# relay_ladder.net
KiCad netlist of a schematic drawn in Altium Designer
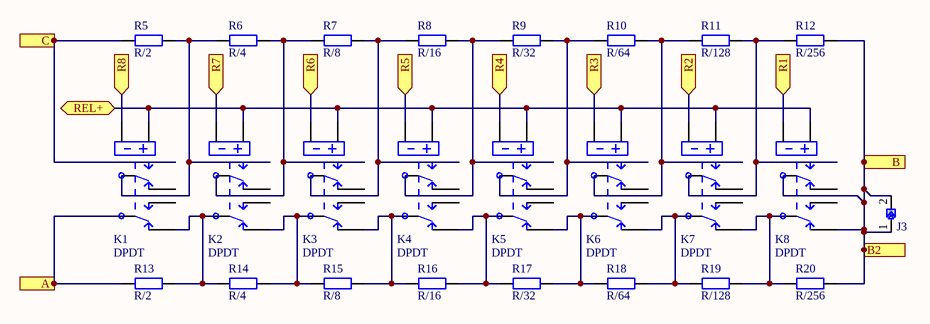
[diagram p0: relay_ladder.SchDoc]

(export (version "E")
  (design (tool "Eeschema 10.0.6"))
  (components
    (comp (ref "J3")
      (value "solder_jumper")
      (footprint "SOLDER_JUMPER_SQUARE")
      (libsource (lib "components_library") (part "solder_jumper"))
    )
    (comp (ref "K1")
      (value "DPDT")
      (footprint "AXICOM IM-G Relay")
      (description "TE CONNECTIVITY  IM-GR  RELAY, DPDT, NO")
      (libsource (lib "components_library") (part "IM-GR Relay DPDT"))
    )
    (comp (ref "K2")
      (value "DPDT")
      (footprint "AXICOM IM-G Relay")
      (description "TE CONNECTIVITY  IM-GR  RELAY, DPDT, NO")
      (libsource (lib "components_library") (part "IM-GR Relay DPDT"))
    )
    (comp (ref "K3")
      (value "DPDT")
      (footprint "AXICOM IM-G Relay")
      (description "TE CONNECTIVITY  IM-GR  RELAY, DPDT, NO")
      (libsource (lib "components_library") (part "IM-GR Relay DPDT"))
    )
    (comp (ref "K4")
      (value "DPDT")
      (footprint "AXICOM IM-G Relay")
      (description "TE CONNECTIVITY  IM-GR  RELAY, DPDT, NO")
      (libsource (lib "components_library") (part "IM-GR Relay DPDT"))
    )
    (comp (ref "K5")
      (value "DPDT")
      (footprint "AXICOM IM-G Relay")
      (description "TE CONNECTIVITY  IM-GR  RELAY, DPDT, NO")
      (libsource (lib "components_library") (part "IM-GR Relay DPDT"))
    )
    (comp (ref "K6")
      (value "DPDT")
      (footprint "AXICOM IM-G Relay")
      (description "TE CONNECTIVITY  IM-GR  RELAY, DPDT, NO")
      (libsource (lib "components_library") (part "IM-GR Relay DPDT"))
    )
    (comp (ref "K7")
      (value "DPDT")
      (footprint "AXICOM IM-G Relay")
      (description "TE CONNECTIVITY  IM-GR  RELAY, DPDT, NO")
      (libsource (lib "components_library") (part "IM-GR Relay DPDT"))
    )
    (comp (ref "K8")
      (value "DPDT")
      (footprint "AXICOM IM-G Relay")
      (description "TE CONNECTIVITY  IM-GR  RELAY, DPDT, NO")
      (libsource (lib "components_library") (part "IM-GR Relay DPDT"))
    )
    (comp (ref "R5")
      (value "R/2")
      (footprint "R2012_0805I_L")
      (description "R")
      (libsource (lib "General") (part "R"))
    )
    (comp (ref "R6")
      (value "R/4")
      (footprint "R2012_0805I_L")
      (description "R")
      (libsource (lib "General") (part "R"))
    )
    (comp (ref "R7")
      (value "R/8")
      (footprint "R2012_0805I_L")
      (description "R")
      (libsource (lib "General") (part "R"))
    )
    (comp (ref "R8")
      (value "R/16")
      (footprint "R2012_0805I_L")
      (description "R")
      (libsource (lib "General") (part "R"))
    )
    (comp (ref "R9")
      (value "R/32")
      (footprint "R2012_0805I_L")
      (description "R")
      (libsource (lib "General") (part "R"))
    )
    (comp (ref "R10")
      (value "R/64")
      (footprint "R2012_0805I_L")
      (description "R")
      (libsource (lib "General") (part "R"))
    )
    (comp (ref "R11")
      (value "R/128")
      (footprint "R2012_0805I_L")
      (description "R")
      (libsource (lib "General") (part "R"))
    )
    (comp (ref "R12")
      (value "R/256")
      (footprint "R2012_0805I_L")
      (description "R")
      (libsource (lib "General") (part "R"))
    )
    (comp (ref "R13")
      (value "R/2")
      (footprint "R2012_0805I_L")
      (description "R")
      (libsource (lib "General") (part "R"))
    )
    (comp (ref "R14")
      (value "R/4")
      (footprint "R2012_0805I_L")
      (description "R")
      (libsource (lib "General") (part "R"))
    )
    (comp (ref "R15")
      (value "R/8")
      (footprint "R2012_0805I_L")
      (description "R")
      (libsource (lib "General") (part "R"))
    )
    (comp (ref "R16")
      (value "R/16")
      (footprint "R2012_0805I_L")
      (description "R")
      (libsource (lib "General") (part "R"))
    )
    (comp (ref "R17")
      (value "R/32")
      (footprint "R2012_0805I_L")
      (description "R")
      (libsource (lib "General") (part "R"))
    )
    (comp (ref "R18")
      (value "R/64")
      (footprint "R2012_0805I_L")
      (description "R")
      (libsource (lib "General") (part "R"))
    )
    (comp (ref "R19")
      (value "R/128")
      (footprint "R2012_0805I_L")
      (description "R")
      (libsource (lib "General") (part "R"))
    )
    (comp (ref "R20")
      (value "R/256")
      (footprint "R2012_0805I_L")
      (description "R")
      (libsource (lib "General") (part "R"))
    )
  )
  (nets
    (net (code "1") (name "/A") (class "Default")
      (node (ref "K1") (pin "6") (pinfunction "6_6") (pintype "passive"))
      (node (ref "R13") (pin "1") (pintype "passive"))
    )
    (net (code "2") (name "/B") (class "Default")
      (node (ref "J3") (pin "1") (pintype "passive"))
      (node (ref "J3") (pin "2") (pintype "passive"))
      (node (ref "K8") (pin "3") (pinfunction "3_3") (pintype "passive"))
      (node (ref "K8") (pin "7") (pinfunction "7_7") (pintype "passive"))
      (node (ref "R12") (pin "2") (pintype "passive"))
      (node (ref "R20") (pin "2") (pintype "passive"))
    )
    (net (code "3") (name "/C") (class "Default")
      (node (ref "K1") (pin "4") (pinfunction "4_4") (pintype "passive"))
      (node (ref "R5") (pin "1") (pintype "passive"))
    )
    (net (code "4") (name "/R1") (class "Default")
      (node (ref "K8") (pin "8") (pinfunction "8_8") (pintype "passive"))
    )
    (net (code "5") (name "/R2") (class "Default")
      (node (ref "K7") (pin "8") (pinfunction "8_8") (pintype "passive"))
    )
    (net (code "6") (name "/R3") (class "Default")
      (node (ref "K6") (pin "8") (pinfunction "8_8") (pintype "passive"))
    )
    (net (code "7") (name "/R4") (class "Default")
      (node (ref "K5") (pin "8") (pinfunction "8_8") (pintype "passive"))
    )
    (net (code "8") (name "/R5") (class "Default")
      (node (ref "K4") (pin "8") (pinfunction "8_8") (pintype "passive"))
    )
    (net (code "9") (name "/R6") (class "Default")
      (node (ref "K3") (pin "8") (pinfunction "8_8") (pintype "passive"))
    )
    (net (code "10") (name "/R7") (class "Default")
      (node (ref "K2") (pin "8") (pinfunction "8_8") (pintype "passive"))
    )
    (net (code "11") (name "/R8") (class "Default")
      (node (ref "K1") (pin "8") (pinfunction "8_8") (pintype "passive"))
    )
    (net (code "12") (name "/REL+") (class "Default")
      (node (ref "K1") (pin "1") (pinfunction "1_1") (pintype "passive"))
      (node (ref "K2") (pin "1") (pinfunction "1_1") (pintype "passive"))
      (node (ref "K3") (pin "1") (pinfunction "1_1") (pintype "passive"))
      (node (ref "K4") (pin "1") (pinfunction "1_1") (pintype "passive"))
      (node (ref "K5") (pin "1") (pinfunction "1_1") (pintype "passive"))
      (node (ref "K6") (pin "1") (pinfunction "1_1") (pintype "passive"))
      (node (ref "K7") (pin "1") (pinfunction "1_1") (pintype "passive"))
      (node (ref "K8") (pin "1") (pinfunction "1_1") (pintype "passive"))
    )
    (net (code "13") (name "Net-(K1-Pad3)") (class "Default")
      (node (ref "K1") (pin "3") (pinfunction "3_3") (pintype "passive"))
      (node (ref "K2") (pin "4") (pinfunction "4_4") (pintype "passive"))
      (node (ref "R5") (pin "2") (pintype "passive"))
      (node (ref "R6") (pin "1") (pintype "passive"))
    )
    (net (code "14") (name "Net-(K1-Pad7)") (class "Default")
      (node (ref "K1") (pin "7") (pinfunction "7_7") (pintype "passive"))
      (node (ref "K2") (pin "6") (pinfunction "6_6") (pintype "passive"))
      (node (ref "R13") (pin "2") (pintype "passive"))
      (node (ref "R14") (pin "1") (pintype "passive"))
    )
    (net (code "15") (name "Net-(K2-Pad3)") (class "Default")
      (node (ref "K2") (pin "3") (pinfunction "3_3") (pintype "passive"))
      (node (ref "K3") (pin "4") (pinfunction "4_4") (pintype "passive"))
      (node (ref "R6") (pin "2") (pintype "passive"))
      (node (ref "R7") (pin "1") (pintype "passive"))
    )
    (net (code "16") (name "Net-(K2-Pad7)") (class "Default")
      (node (ref "K2") (pin "7") (pinfunction "7_7") (pintype "passive"))
      (node (ref "K3") (pin "6") (pinfunction "6_6") (pintype "passive"))
      (node (ref "R14") (pin "2") (pintype "passive"))
      (node (ref "R15") (pin "1") (pintype "passive"))
    )
    (net (code "17") (name "Net-(K3-Pad3)") (class "Default")
      (node (ref "K3") (pin "3") (pinfunction "3_3") (pintype "passive"))
      (node (ref "K4") (pin "4") (pinfunction "4_4") (pintype "passive"))
      (node (ref "R7") (pin "2") (pintype "passive"))
      (node (ref "R8") (pin "1") (pintype "passive"))
    )
    (net (code "18") (name "Net-(K3-Pad7)") (class "Default")
      (node (ref "K3") (pin "7") (pinfunction "7_7") (pintype "passive"))
      (node (ref "K4") (pin "6") (pinfunction "6_6") (pintype "passive"))
      (node (ref "R15") (pin "2") (pintype "passive"))
      (node (ref "R16") (pin "1") (pintype "passive"))
    )
    (net (code "19") (name "Net-(K4-Pad3)") (class "Default")
      (node (ref "K4") (pin "3") (pinfunction "3_3") (pintype "passive"))
      (node (ref "K5") (pin "4") (pinfunction "4_4") (pintype "passive"))
      (node (ref "R8") (pin "2") (pintype "passive"))
      (node (ref "R9") (pin "1") (pintype "passive"))
    )
    (net (code "20") (name "Net-(K4-Pad7)") (class "Default")
      (node (ref "K4") (pin "7") (pinfunction "7_7") (pintype "passive"))
      (node (ref "K5") (pin "6") (pinfunction "6_6") (pintype "passive"))
      (node (ref "R16") (pin "2") (pintype "passive"))
      (node (ref "R17") (pin "1") (pintype "passive"))
    )
    (net (code "21") (name "Net-(K5-Pad3)") (class "Default")
      (node (ref "K5") (pin "3") (pinfunction "3_3") (pintype "passive"))
      (node (ref "K6") (pin "4") (pinfunction "4_4") (pintype "passive"))
      (node (ref "R10") (pin "1") (pintype "passive"))
      (node (ref "R9") (pin "2") (pintype "passive"))
    )
    (net (code "22") (name "Net-(K5-Pad7)") (class "Default")
      (node (ref "K5") (pin "7") (pinfunction "7_7") (pintype "passive"))
      (node (ref "K6") (pin "6") (pinfunction "6_6") (pintype "passive"))
      (node (ref "R17") (pin "2") (pintype "passive"))
      (node (ref "R18") (pin "1") (pintype "passive"))
    )
    (net (code "23") (name "Net-(K6-Pad3)") (class "Default")
      (node (ref "K6") (pin "3") (pinfunction "3_3") (pintype "passive"))
      (node (ref "K7") (pin "4") (pinfunction "4_4") (pintype "passive"))
      (node (ref "R10") (pin "2") (pintype "passive"))
      (node (ref "R11") (pin "1") (pintype "passive"))
    )
    (net (code "24") (name "Net-(K6-Pad7)") (class "Default")
      (node (ref "K6") (pin "7") (pinfunction "7_7") (pintype "passive"))
      (node (ref "K7") (pin "6") (pinfunction "6_6") (pintype "passive"))
      (node (ref "R18") (pin "2") (pintype "passive"))
      (node (ref "R19") (pin "1") (pintype "passive"))
    )
    (net (code "25") (name "Net-(K7-Pad3)") (class "Default")
      (node (ref "K7") (pin "3") (pinfunction "3_3") (pintype "passive"))
      (node (ref "K8") (pin "4") (pinfunction "4_4") (pintype "passive"))
      (node (ref "R11") (pin "2") (pintype "passive"))
      (node (ref "R12") (pin "1") (pintype "passive"))
    )
    (net (code "26") (name "Net-(K7-Pad7)") (class "Default")
      (node (ref "K7") (pin "7") (pinfunction "7_7") (pintype "passive"))
      (node (ref "K8") (pin "6") (pinfunction "6_6") (pintype "passive"))
      (node (ref "R19") (pin "2") (pintype "passive"))
      (node (ref "R20") (pin "1") (pintype "passive"))
    )
    (net (code "27") (name "unconnected-(K1-Pad2)") (class "Default")
      (node (ref "K1") (pin "2") (pinfunction "2_2") (pintype "passive"))
    )
    (net (code "28") (name "unconnected-(K1-Pad5)") (class "Default")
      (node (ref "K1") (pin "5") (pinfunction "5_5") (pintype "passive"))
    )
    (net (code "29") (name "unconnected-(K2-Pad2)") (class "Default")
      (node (ref "K2") (pin "2") (pinfunction "2_2") (pintype "passive"))
    )
    (net (code "30") (name "unconnected-(K2-Pad5)") (class "Default")
      (node (ref "K2") (pin "5") (pinfunction "5_5") (pintype "passive"))
    )
    (net (code "31") (name "unconnected-(K3-Pad2)") (class "Default")
      (node (ref "K3") (pin "2") (pinfunction "2_2") (pintype "passive"))
    )
    (net (code "32") (name "unconnected-(K3-Pad5)") (class "Default")
      (node (ref "K3") (pin "5") (pinfunction "5_5") (pintype "passive"))
    )
    (net (code "33") (name "unconnected-(K4-Pad2)") (class "Default")
      (node (ref "K4") (pin "2") (pinfunction "2_2") (pintype "passive"))
    )
    (net (code "34") (name "unconnected-(K4-Pad5)") (class "Default")
      (node (ref "K4") (pin "5") (pinfunction "5_5") (pintype "passive"))
    )
    (net (code "35") (name "unconnected-(K5-Pad2)") (class "Default")
      (node (ref "K5") (pin "2") (pinfunction "2_2") (pintype "passive"))
    )
    (net (code "36") (name "unconnected-(K5-Pad5)") (class "Default")
      (node (ref "K5") (pin "5") (pinfunction "5_5") (pintype "passive"))
    )
    (net (code "37") (name "unconnected-(K6-Pad2)") (class "Default")
      (node (ref "K6") (pin "2") (pinfunction "2_2") (pintype "passive"))
    )
    (net (code "38") (name "unconnected-(K6-Pad5)") (class "Default")
      (node (ref "K6") (pin "5") (pinfunction "5_5") (pintype "passive"))
    )
    (net (code "39") (name "unconnected-(K7-Pad2)") (class "Default")
      (node (ref "K7") (pin "2") (pinfunction "2_2") (pintype "passive"))
    )
    (net (code "40") (name "unconnected-(K7-Pad5)") (class "Default")
      (node (ref "K7") (pin "5") (pinfunction "5_5") (pintype "passive"))
    )
    (net (code "41") (name "unconnected-(K8-Pad2)") (class "Default")
      (node (ref "K8") (pin "2") (pinfunction "2_2") (pintype "passive"))
    )
    (net (code "42") (name "unconnected-(K8-Pad5)") (class "Default")
      (node (ref "K8") (pin "5") (pinfunction "5_5") (pintype "passive"))
    )
  )
)
